# fnordstripe.net
KiCad netlist of a schematic drawn in EAGLE
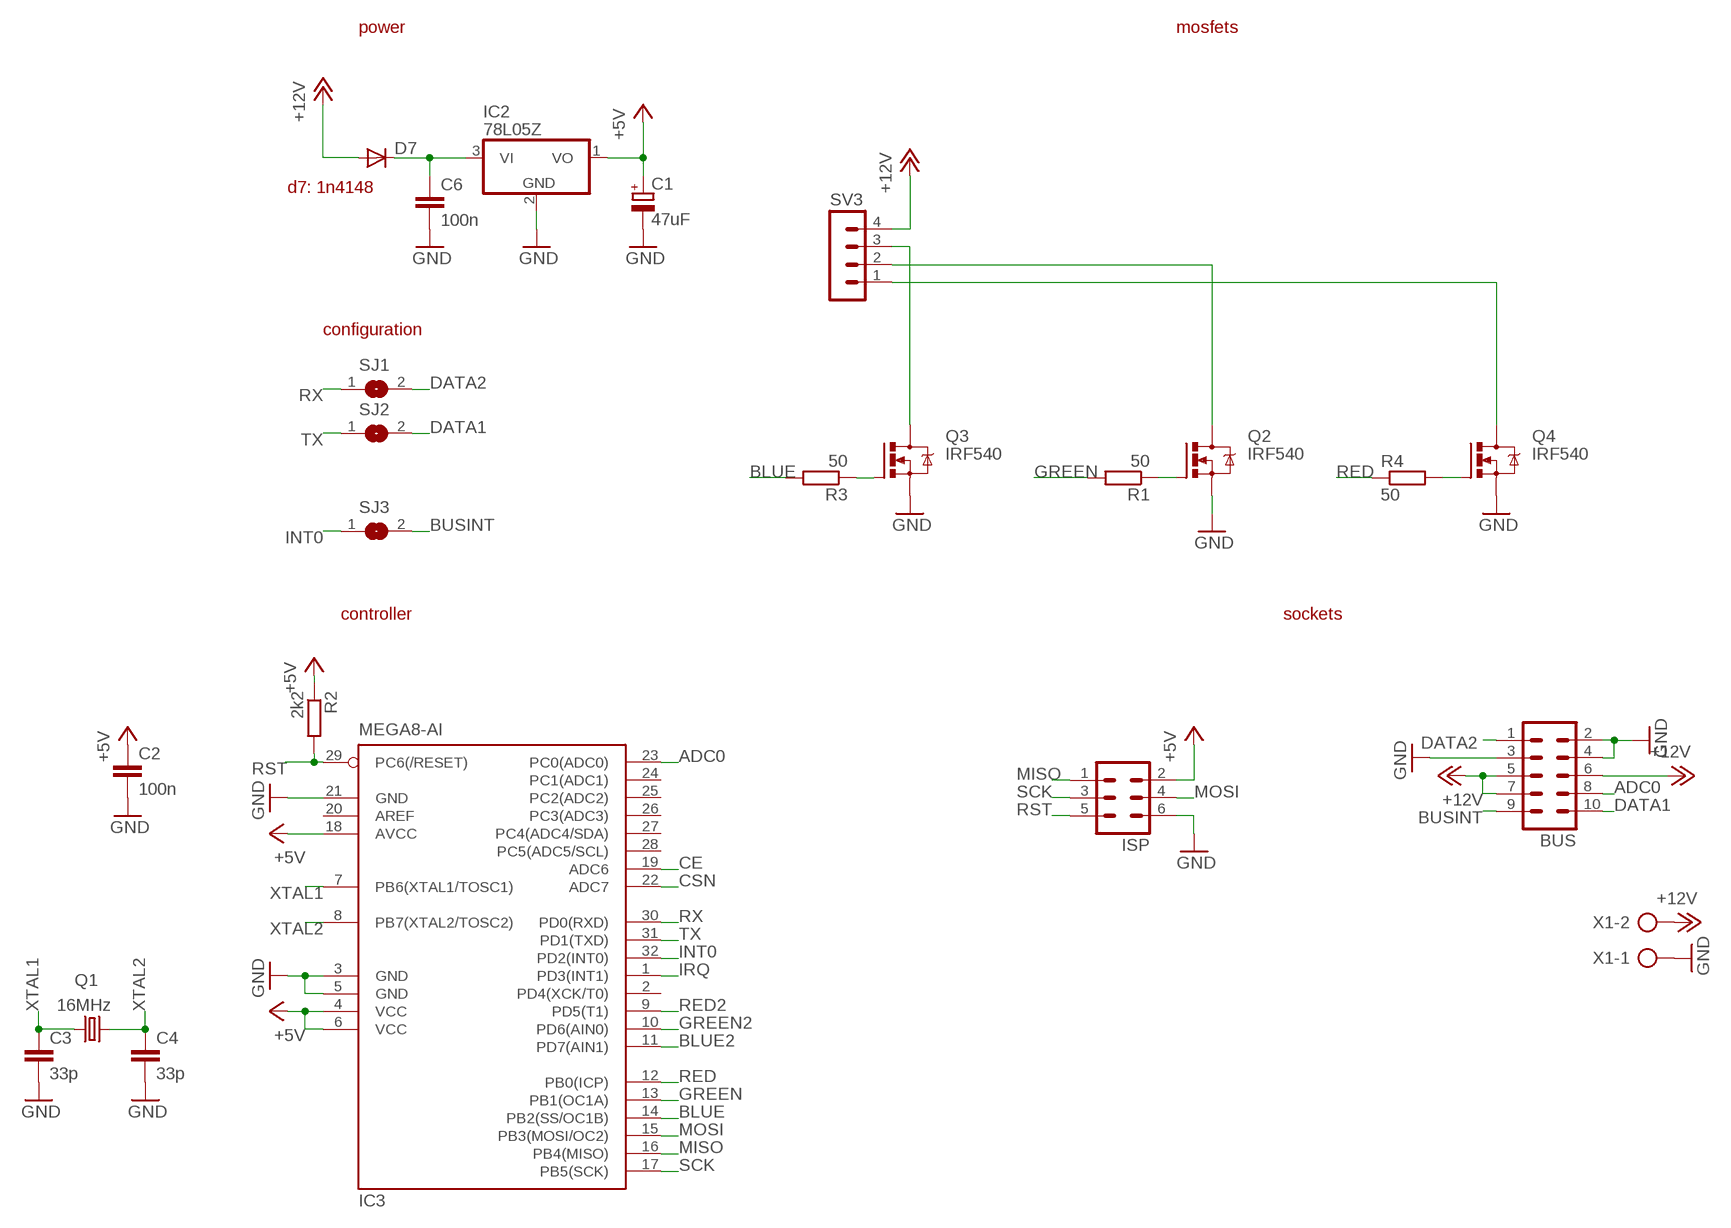
[diagram p0: schematic, sheet 1]

(export (version "E")
  (design (tool "Eeschema 10.0.6"))
  (components
    (comp (ref "BUS")
      (value "MA05-2")
      (footprint "eagle-import:MA05-2")
      (libsource (lib "eagle-import") (part "MA05-2"))
    )
    (comp (ref "C1")
      (value "47uF")
      (footprint "eagle-import:E2-5")
      (libsource (lib "eagle-import") (part "CPOL-EUE2-5"))
    )
    (comp (ref "C2")
      (value "100n")
      (footprint "eagle-import:C025-024X044")
      (libsource (lib "eagle-import") (part "C-EU025-024X044"))
    )
    (comp (ref "C3")
      (value "33p")
      (footprint "eagle-import:C025-024X044")
      (libsource (lib "eagle-import") (part "C-EU025-024X044"))
    )
    (comp (ref "C4")
      (value "33p")
      (footprint "eagle-import:C025-024X044")
      (libsource (lib "eagle-import") (part "C-EU025-024X044"))
    )
    (comp (ref "C6")
      (value "100n")
      (footprint "eagle-import:C025-024X044")
      (libsource (lib "eagle-import") (part "C-EU025-024X044"))
    )
    (comp (ref "D7")
      (value "DIODE-D-2.5")
      (footprint "eagle-import:D-2.5")
      (libsource (lib "eagle-import") (part "DIODE-D-2.5"))
    )
    (comp (ref "IC2")
      (value "78L05Z")
      (footprint "eagle-import:TO92")
      (libsource (lib "eagle-import") (part "78ZL05"))
    )
    (comp (ref "IC3")
      (value "MEGA8-AI")
      (footprint "eagle-import:TQFP32-08")
      (fields (field (name "MPN") "ATMEGA8-16AU"))
      (libsource (lib "eagle-import") (part "MEGA8-AI"))
    )
    (comp (ref "ISP")
      (value "MA03-2")
      (footprint "eagle-import:MA03-2")
      (libsource (lib "eagle-import") (part "MA03-2"))
    )
    (comp (ref "Q1")
      (value "16MHz")
      (footprint "eagle-import:HC49U-V")
      (libsource (lib "eagle-import") (part "CRYSTALHC49U-V"))
    )
    (comp (ref "Q2")
      (value "IRF540")
      (footprint "eagle-import:TO220BV")
      (libsource (lib "eagle-import") (part "IRF540"))
    )
    (comp (ref "Q3")
      (value "IRF540")
      (footprint "eagle-import:TO220BV")
      (libsource (lib "eagle-import") (part "IRF540"))
    )
    (comp (ref "Q4")
      (value "IRF540")
      (footprint "eagle-import:TO220BV")
      (libsource (lib "eagle-import") (part "IRF540"))
    )
    (comp (ref "R1")
      (value "50")
      (footprint "eagle-import:0204V")
      (libsource (lib "eagle-import") (part "R-EU_0204/2V"))
    )
    (comp (ref "R2")
      (value "2k2")
      (footprint "eagle-import:0204V")
      (libsource (lib "eagle-import") (part "R-EU_0204/2V"))
    )
    (comp (ref "R3")
      (value "50")
      (footprint "eagle-import:0204V")
      (libsource (lib "eagle-import") (part "R-EU_0204/2V"))
    )
    (comp (ref "R4")
      (value "50")
      (footprint "eagle-import:0204V")
      (libsource (lib "eagle-import") (part "R-EU_0204/2V"))
    )
    (comp (ref "SJ1") (value "SJ") (footprint "eagle-import:SJ") (libsource (lib "eagle-import") (part "SJ")))
    (comp (ref "SJ2") (value "SJ") (footprint "eagle-import:SJ") (libsource (lib "eagle-import") (part "SJ")))
    (comp (ref "SJ3") (value "SJ") (footprint "eagle-import:SJ") (libsource (lib "eagle-import") (part "SJ")))
    (comp (ref "SV3")
      (value "MA04-1")
      (footprint "eagle-import:MA04-1")
      (libsource (lib "eagle-import") (part "MA04-1"))
    )
    (comp (ref "X1")
      (value "AK500/2")
      (footprint "eagle-import:AK500_2")
      (libsource (lib "eagle-import") (part "AK500/2"))
    )
  )
  (nets
    (net (code "1") (name "+5V") (class "Default")
      (node (ref "C1") (pin "+") (pinfunction "+_+") (pintype "passive"))
      (node (ref "C2") (pin "1") (pinfunction "1_1") (pintype "passive"))
      (node (ref "IC2") (pin "1") (pinfunction "VO_1") (pintype "passive"))
      (node (ref "IC3") (pin "18") (pinfunction "AVCC_18") (pintype "power_in"))
      (node (ref "IC3") (pin "4") (pinfunction "VCC_4") (pintype "power_in"))
      (node (ref "IC3") (pin "6") (pinfunction "VCC_6") (pintype "power_in"))
      (node (ref "ISP") (pin "2") (pinfunction "2_2") (pintype "passive"))
      (node (ref "R2") (pin "1") (pinfunction "1_1") (pintype "passive"))
    )
    (net (code "2") (name "+12V") (class "Default")
      (node (ref "BUS") (pin "5") (pinfunction "5_5") (pintype "passive"))
      (node (ref "BUS") (pin "6") (pinfunction "6_6") (pintype "passive"))
      (node (ref "BUS") (pin "7") (pinfunction "7_7") (pintype "passive"))
      (node (ref "D7") (pin "A") (pinfunction "A_A") (pintype "passive"))
      (node (ref "SV3") (pin "4") (pinfunction "4_4") (pintype "passive"))
      (node (ref "X1") (pin "2") (pinfunction "KL_2") (pintype "passive"))
    )
    (net (code "3") (name "/ADC0") (class "Default")
      (node (ref "BUS") (pin "8") (pinfunction "8_8") (pintype "passive"))
      (node (ref "IC3") (pin "23") (pinfunction "PC0(ADC0)_23") (pintype "bidirectional"))
    )
    (net (code "4") (name "/BLUE") (class "Default")
      (node (ref "IC3") (pin "14") (pinfunction "PB2(SS/OC1B)_14") (pintype "bidirectional"))
      (node (ref "R3") (pin "2") (pinfunction "2_2") (pintype "passive"))
    )
    (net (code "5") (name "/BLUE2") (class "Default")
      (node (ref "IC3") (pin "11") (pinfunction "PD7(AIN1)_11") (pintype "bidirectional"))
    )
    (net (code "6") (name "/BUSINT") (class "Default")
      (node (ref "BUS") (pin "9") (pinfunction "9_9") (pintype "passive"))
      (node (ref "SJ3") (pin "2") (pinfunction "2_2") (pintype "passive"))
    )
    (net (code "7") (name "/CE") (class "Default")
      (node (ref "IC3") (pin "19") (pinfunction "ADC6_19") (pintype "bidirectional"))
    )
    (net (code "8") (name "/CSN") (class "Default")
      (node (ref "IC3") (pin "22") (pinfunction "ADC7_22") (pintype "bidirectional"))
    )
    (net (code "9") (name "/DATA1") (class "Default")
      (node (ref "BUS") (pin "10") (pinfunction "10_10") (pintype "passive"))
      (node (ref "SJ2") (pin "2") (pinfunction "2_2") (pintype "passive"))
    )
    (net (code "10") (name "/DATA2") (class "Default")
      (node (ref "BUS") (pin "1") (pinfunction "1_1") (pintype "passive"))
      (node (ref "SJ1") (pin "2") (pinfunction "2_2") (pintype "passive"))
    )
    (net (code "11") (name "/GREEN") (class "Default")
      (node (ref "IC3") (pin "13") (pinfunction "PB1(OC1A)_13") (pintype "bidirectional"))
      (node (ref "R1") (pin "2") (pinfunction "2_2") (pintype "passive"))
    )
    (net (code "12") (name "/GREEN2") (class "Default")
      (node (ref "IC3") (pin "10") (pinfunction "PD6(AIN0)_10") (pintype "bidirectional"))
    )
    (net (code "13") (name "/INT0") (class "Default")
      (node (ref "IC3") (pin "32") (pinfunction "PD2(INT0)_32") (pintype "bidirectional"))
      (node (ref "SJ3") (pin "1") (pinfunction "1_1") (pintype "passive"))
    )
    (net (code "14") (name "/IRQ") (class "Default")
      (node (ref "IC3") (pin "1") (pinfunction "PD3(INT1)_1") (pintype "bidirectional"))
    )
    (net (code "15") (name "/MISO") (class "Default")
      (node (ref "IC3") (pin "16") (pinfunction "PB4(MISO)_16") (pintype "bidirectional"))
      (node (ref "ISP") (pin "1") (pinfunction "1_1") (pintype "passive"))
    )
    (net (code "16") (name "/MOSI") (class "Default")
      (node (ref "IC3") (pin "15") (pinfunction "PB3(MOSI/OC2)_15") (pintype "bidirectional"))
      (node (ref "ISP") (pin "4") (pinfunction "4_4") (pintype "passive"))
    )
    (net (code "17") (name "/RED") (class "Default")
      (node (ref "IC3") (pin "12") (pinfunction "PB0(ICP)_12") (pintype "bidirectional"))
      (node (ref "R4") (pin "1") (pinfunction "1_1") (pintype "passive"))
    )
    (net (code "18") (name "/RED2") (class "Default")
      (node (ref "IC3") (pin "9") (pinfunction "PD5(T1)_9") (pintype "bidirectional"))
    )
    (net (code "19") (name "/RST") (class "Default")
      (node (ref "IC3") (pin "29") (pinfunction "PC6(/RESET)_29") (pintype "bidirectional"))
      (node (ref "ISP") (pin "5") (pinfunction "5_5") (pintype "passive"))
      (node (ref "R2") (pin "2") (pinfunction "2_2") (pintype "passive"))
    )
    (net (code "20") (name "/RX") (class "Default")
      (node (ref "IC3") (pin "30") (pinfunction "PD0(RXD)_30") (pintype "bidirectional"))
      (node (ref "SJ1") (pin "1") (pinfunction "1_1") (pintype "passive"))
    )
    (net (code "21") (name "/SCK") (class "Default")
      (node (ref "IC3") (pin "17") (pinfunction "PB5(SCK)_17") (pintype "bidirectional"))
      (node (ref "ISP") (pin "3") (pinfunction "3_3") (pintype "passive"))
    )
    (net (code "22") (name "/TX") (class "Default")
      (node (ref "IC3") (pin "31") (pinfunction "PD1(TXD)_31") (pintype "bidirectional"))
      (node (ref "SJ2") (pin "1") (pinfunction "1_1") (pintype "passive"))
    )
    (net (code "23") (name "/XTAL1") (class "Default")
      (node (ref "C3") (pin "1") (pinfunction "1_1") (pintype "passive"))
      (node (ref "IC3") (pin "7") (pinfunction "PB6(XTAL1/TOSC1)_7") (pintype "bidirectional"))
      (node (ref "Q1") (pin "1") (pinfunction "1_1") (pintype "passive"))
    )
    (net (code "24") (name "/XTAL2") (class "Default")
      (node (ref "C4") (pin "1") (pinfunction "1_1") (pintype "passive"))
      (node (ref "IC3") (pin "8") (pinfunction "PB7(XTAL2/TOSC2)_8") (pintype "bidirectional"))
      (node (ref "Q1") (pin "2") (pinfunction "2_2") (pintype "passive"))
    )
    (net (code "25") (name "GND") (class "Default")
      (node (ref "BUS") (pin "2") (pinfunction "2_2") (pintype "passive"))
      (node (ref "BUS") (pin "3") (pinfunction "3_3") (pintype "passive"))
      (node (ref "BUS") (pin "4") (pinfunction "4_4") (pintype "passive"))
      (node (ref "C1") (pin "-") (pinfunction "-_-") (pintype "passive"))
      (node (ref "C2") (pin "2") (pinfunction "2_2") (pintype "passive"))
      (node (ref "C3") (pin "2") (pinfunction "2_2") (pintype "passive"))
      (node (ref "C4") (pin "2") (pinfunction "2_2") (pintype "passive"))
      (node (ref "C6") (pin "2") (pinfunction "2_2") (pintype "passive"))
      (node (ref "IC2") (pin "2") (pinfunction "GND_2") (pintype "passive"))
      (node (ref "IC3") (pin "21") (pinfunction "GND_21") (pintype "power_in"))
      (node (ref "IC3") (pin "3") (pinfunction "GND_3") (pintype "power_in"))
      (node (ref "IC3") (pin "5") (pinfunction "GND_5") (pintype "power_in"))
      (node (ref "ISP") (pin "6") (pinfunction "6_6") (pintype "passive"))
      (node (ref "Q2") (pin "S") (pinfunction "S_S") (pintype "passive"))
      (node (ref "Q3") (pin "S") (pinfunction "S_S") (pintype "passive"))
      (node (ref "Q4") (pin "S") (pinfunction "S_S") (pintype "passive"))
      (node (ref "X1") (pin "1") (pinfunction "KL_1") (pintype "passive"))
    )
    (net (code "26") (name "Net-(IC2-VI)") (class "Default")
      (node (ref "C6") (pin "1") (pinfunction "1_1") (pintype "passive"))
      (node (ref "D7") (pin "C") (pinfunction "C_C") (pintype "passive"))
      (node (ref "IC2") (pin "3") (pinfunction "VI_3") (pintype "input"))
    )
    (net (code "27") (name "Net-(Q2-PadD)") (class "Default")
      (node (ref "Q2") (pin "D") (pinfunction "D_D") (pintype "passive"))
      (node (ref "SV3") (pin "2") (pinfunction "2_2") (pintype "passive"))
    )
    (net (code "28") (name "Net-(Q2-PadG)") (class "Default")
      (node (ref "Q2") (pin "G") (pinfunction "G_G") (pintype "passive"))
      (node (ref "R1") (pin "1") (pinfunction "1_1") (pintype "passive"))
    )
    (net (code "29") (name "Net-(Q3-PadD)") (class "Default")
      (node (ref "Q3") (pin "D") (pinfunction "D_D") (pintype "passive"))
      (node (ref "SV3") (pin "3") (pinfunction "3_3") (pintype "passive"))
    )
    (net (code "30") (name "Net-(Q3-PadG)") (class "Default")
      (node (ref "Q3") (pin "G") (pinfunction "G_G") (pintype "passive"))
      (node (ref "R3") (pin "1") (pinfunction "1_1") (pintype "passive"))
    )
    (net (code "31") (name "Net-(Q4-PadD)") (class "Default")
      (node (ref "Q4") (pin "D") (pinfunction "D_D") (pintype "passive"))
      (node (ref "SV3") (pin "1") (pinfunction "1_1") (pintype "passive"))
    )
    (net (code "32") (name "Net-(Q4-PadG)") (class "Default")
      (node (ref "Q4") (pin "G") (pinfunction "G_G") (pintype "passive"))
      (node (ref "R4") (pin "2") (pinfunction "2_2") (pintype "passive"))
    )
    (net (code "33") (name "unconnected-(IC3-AREF-Pad20)") (class "Default")
      (node (ref "IC3") (pin "20") (pinfunction "AREF_20") (pintype "passive"))
    )
    (net (code "34") (name "unconnected-(IC3-PC1(ADC1)-Pad24)") (class "Default")
      (node (ref "IC3") (pin "24") (pinfunction "PC1(ADC1)_24") (pintype "bidirectional"))
    )
    (net (code "35") (name "unconnected-(IC3-PC2(ADC2)-Pad25)") (class "Default")
      (node (ref "IC3") (pin "25") (pinfunction "PC2(ADC2)_25") (pintype "bidirectional"))
    )
    (net (code "36") (name "unconnected-(IC3-PC3(ADC3)-Pad26)") (class "Default")
      (node (ref "IC3") (pin "26") (pinfunction "PC3(ADC3)_26") (pintype "bidirectional"))
    )
    (net (code "37") (name "unconnected-(IC3-PC4(ADC4{slash}SDA)-Pad27)") (class "Default")
      (node (ref "IC3") (pin "27") (pinfunction "PC4(ADC4/SDA)_27") (pintype "bidirectional"))
    )
    (net (code "38") (name "unconnected-(IC3-PC5(ADC5{slash}SCL)-Pad28)") (class "Default")
      (node (ref "IC3") (pin "28") (pinfunction "PC5(ADC5/SCL)_28") (pintype "bidirectional"))
    )
    (net (code "39") (name "unconnected-(IC3-PD4(XCK{slash}T0)-Pad2)") (class "Default")
      (node (ref "IC3") (pin "2") (pinfunction "PD4(XCK/T0)_2") (pintype "bidirectional"))
    )
  )
)
